# 06_LMS7002M_RF2.net
KiCad netlist of a schematic drawn in Altium Designer
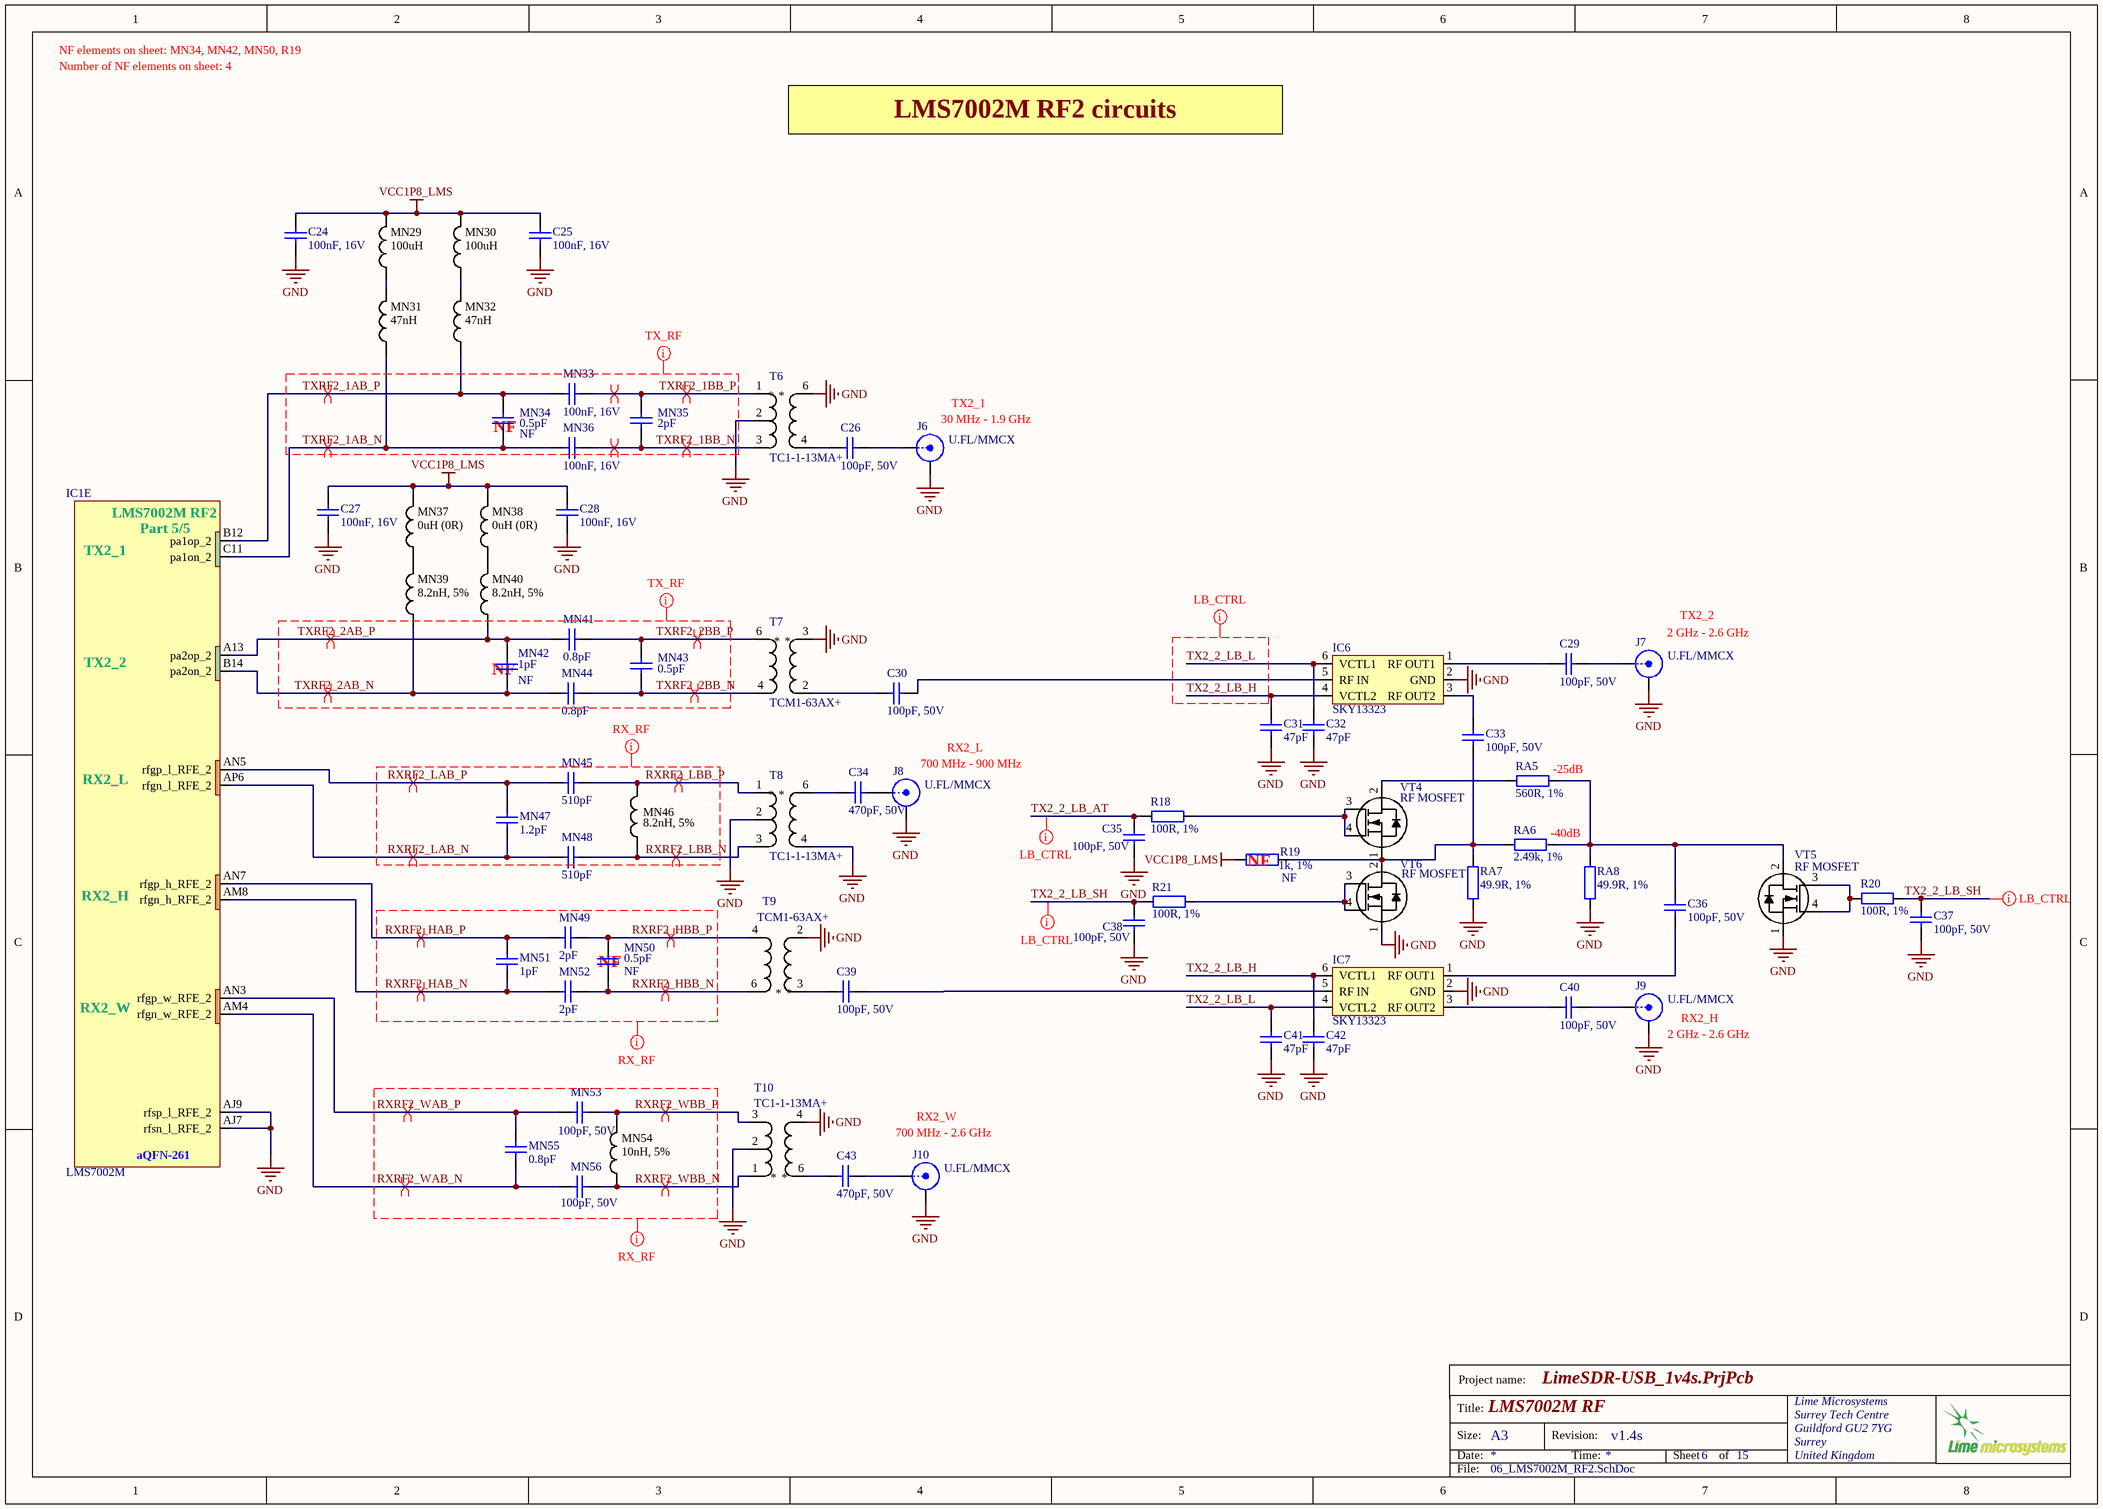
[diagram p0: 06_LMS7002M_RF2.SchDoc]

(export (version "E")
  (design (tool "Eeschema 10.0.6"))
  (components
    (comp (ref "C24")
      (value "100nF, 16V")
      (footprint "CAP0402")
      (fields
        (field (name "MANUFACTURER") "Murata Electronics")
        (field (name "TOLERANCE") "10 %")
        (field (name "MANUFACTURER PART NUMBER") "GRM155R71C104KA88D")
      )
      (libsource (lib "LimeMicroAltiumLib_schLib") (part "Cap_0402"))
    )
    (comp (ref "C25")
      (value "100nF, 16V")
      (footprint "CAP0402")
      (fields
        (field (name "MANUFACTURER") "Murata Electronics")
        (field (name "TOLERANCE") "10 %")
        (field (name "MANUFACTURER PART NUMBER") "GRM155R71C104KA88D")
      )
      (libsource (lib "LimeMicroAltiumLib_schLib") (part "Cap_0402"))
    )
    (comp (ref "C26")
      (value "100pF, 50V")
      (footprint "CAP0402")
      (fields (field (name "TOLERANCE") "±5%") (field (name "MANUFACTURER") "Yageo"))
      (libsource (lib "LimeMicroAltiumLib_schLib") (part "Cap_0402"))
    )
    (comp (ref "C27")
      (value "100nF, 16V")
      (footprint "CAP0402")
      (fields
        (field (name "MANUFACTURER") "Murata Electronics")
        (field (name "TOLERANCE") "10 %")
        (field (name "MANUFACTURER PART NUMBER") "GRM155R71C104KA88D")
      )
      (libsource (lib "LimeMicroAltiumLib_schLib") (part "Cap_0402"))
    )
    (comp (ref "C28")
      (value "100nF, 16V")
      (footprint "CAP0402")
      (fields
        (field (name "MANUFACTURER") "Murata Electronics")
        (field (name "TOLERANCE") "10 %")
        (field (name "MANUFACTURER PART NUMBER") "GRM155R71C104KA88D")
      )
      (libsource (lib "LimeMicroAltiumLib_schLib") (part "Cap_0402"))
    )
    (comp (ref "C29")
      (value "100pF, 50V")
      (footprint "CAP0402")
      (fields (field (name "TOLERANCE") "±5%") (field (name "MANUFACTURER") "Yageo"))
      (libsource (lib "LimeMicroAltiumLib_schLib") (part "Cap_0402"))
    )
    (comp (ref "C30")
      (value "100pF, 50V")
      (footprint "CAP0402")
      (fields (field (name "TOLERANCE") "±5%") (field (name "MANUFACTURER") "Yageo"))
      (libsource (lib "LimeMicroAltiumLib_schLib") (part "Cap_0402"))
    )
    (comp (ref "C31")
      (value "47pF")
      (footprint "CAP0402")
      (fields (field (name "TOLERANCE") "±1%") (field (name "MANUFACTURER") "TDK Corporation"))
      (libsource (lib "LimeMicroAltiumLib_schLib") (part "Cap_0402"))
    )
    (comp (ref "C32")
      (value "47pF")
      (footprint "CAP0402")
      (fields (field (name "TOLERANCE") "±1%") (field (name "MANUFACTURER") "TDK Corporation"))
      (libsource (lib "LimeMicroAltiumLib_schLib") (part "Cap_0402"))
    )
    (comp (ref "C33")
      (value "100pF, 50V")
      (footprint "CAP0402")
      (fields (field (name "TOLERANCE") "±5%") (field (name "MANUFACTURER") "Yageo"))
      (libsource (lib "LimeMicroAltiumLib_schLib") (part "Cap_0402"))
    )
    (comp (ref "C34")
      (value "470pF, 50V")
      (footprint "CAP0402")
      (fields
        (field (name "MANUFACTURER PART NUMBER") "C1005C0G1H471J050BA")
        (field (name "TOLERANCE") "±5%")
        (field (name "MANUFACTURER") "TDK Corporation")
      )
      (libsource (lib "LimeMicroAltiumLib_schLib") (part "Cap_0402"))
    )
    (comp (ref "C35")
      (value "100pF, 50V")
      (footprint "CAP0402")
      (fields (field (name "TOLERANCE") "±5%") (field (name "MANUFACTURER") "Yageo"))
      (libsource (lib "LimeMicroAltiumLib_schLib") (part "Cap_0402"))
    )
    (comp (ref "C36")
      (value "100pF, 50V")
      (footprint "CAP0402")
      (fields (field (name "TOLERANCE") "±5%") (field (name "MANUFACTURER") "Yageo"))
      (libsource (lib "LimeMicroAltiumLib_schLib") (part "Cap_0402"))
    )
    (comp (ref "C37")
      (value "100pF, 50V")
      (footprint "CAP0402")
      (fields (field (name "TOLERANCE") "±5%") (field (name "MANUFACTURER") "Yageo"))
      (libsource (lib "LimeMicroAltiumLib_schLib") (part "Cap_0402"))
    )
    (comp (ref "C38")
      (value "100pF, 50V")
      (footprint "CAP0402")
      (fields (field (name "TOLERANCE") "±5%") (field (name "MANUFACTURER") "Yageo"))
      (libsource (lib "LimeMicroAltiumLib_schLib") (part "Cap_0402"))
    )
    (comp (ref "C39")
      (value "100pF, 50V")
      (footprint "CAP0402")
      (fields (field (name "TOLERANCE") "±5%") (field (name "MANUFACTURER") "Yageo"))
      (libsource (lib "LimeMicroAltiumLib_schLib") (part "Cap_0402"))
    )
    (comp (ref "C40")
      (value "100pF, 50V")
      (footprint "CAP0402")
      (fields (field (name "TOLERANCE") "±5%") (field (name "MANUFACTURER") "Yageo"))
      (libsource (lib "LimeMicroAltiumLib_schLib") (part "Cap_0402"))
    )
    (comp (ref "C41")
      (value "47pF")
      (footprint "CAP0402")
      (fields (field (name "TOLERANCE") "±1%") (field (name "MANUFACTURER") "TDK Corporation"))
      (libsource (lib "LimeMicroAltiumLib_schLib") (part "Cap_0402"))
    )
    (comp (ref "C42")
      (value "47pF")
      (footprint "CAP0402")
      (fields (field (name "TOLERANCE") "±1%") (field (name "MANUFACTURER") "TDK Corporation"))
      (libsource (lib "LimeMicroAltiumLib_schLib") (part "Cap_0402"))
    )
    (comp (ref "C43")
      (value "470pF, 50V")
      (footprint "CAP0402")
      (fields
        (field (name "MANUFACTURER PART NUMBER") "C1005C0G1H471J050BA")
        (field (name "TOLERANCE") "±5%")
        (field (name "MANUFACTURER") "TDK Corporation")
      )
      (libsource (lib "LimeMicroAltiumLib_schLib") (part "Cap_0402"))
    )
    (comp (ref "IC1")
      (value "LMS7002M")
      (footprint "LMS7002M_v3")
      (fields (field (name "MANUFACTURER") "Lime Microsystems"))
      (libsource (lib "LimeMicroAltiumLib_schLib") (part "LMS7002M"))
    )
    (comp (ref "IC6")
      (value "SKY13323")
      (footprint "SKY13323-378LF")
      (description "SKY13323-378LF: 0.1-3.0 GHz GaAs SPDT Switch")
      (fields (field (name "MANUFACTURER") "Skyworks Solutions Inc."))
      (libsource (lib "LimeMicroAltiumLib_schLib") (part "SKY13323"))
    )
    (comp (ref "IC7")
      (value "SKY13323")
      (footprint "SKY13323-378LF")
      (description "SKY13323-378LF: 0.1-3.0 GHz GaAs SPDT Switch")
      (fields (field (name "MANUFACTURER") "Skyworks Solutions Inc."))
      (libsource (lib "LimeMicroAltiumLib_schLib") (part "SKY13323"))
    )
    (comp (ref "J6")
      (value "U.FL/MMCX")
      (footprint "MMCX_UFL_conn_u")
      (description "CONN UMC RCPT STR 50 OHM SMD")
      (fields (field (name "MANUFACTURER") "Molex, LLC"))
      (libsource (lib "LimeMicroAltiumLib_schLib") (part "RF_IF_connector"))
    )
    (comp (ref "J7")
      (value "U.FL/MMCX")
      (footprint "MMCX_UFL_conn_u")
      (description "CONN UMC RCPT STR 50 OHM SMD")
      (fields (field (name "MANUFACTURER") "Molex, LLC"))
      (libsource (lib "LimeMicroAltiumLib_schLib") (part "RF_IF_connector"))
    )
    (comp (ref "J8")
      (value "U.FL/MMCX")
      (footprint "MMCX_UFL_conn_u")
      (description "CONN UMC RCPT STR 50 OHM SMD")
      (fields (field (name "MANUFACTURER") "Molex, LLC"))
      (libsource (lib "LimeMicroAltiumLib_schLib") (part "RF_IF_connector"))
    )
    (comp (ref "J9")
      (value "U.FL/MMCX")
      (footprint "MMCX_UFL_conn_u")
      (description "CONN UMC RCPT STR 50 OHM SMD")
      (fields (field (name "MANUFACTURER") "Molex, LLC"))
      (libsource (lib "LimeMicroAltiumLib_schLib") (part "RF_IF_connector"))
    )
    (comp (ref "J10")
      (value "U.FL/MMCX")
      (footprint "MMCX_UFL_conn_u")
      (description "CONN UMC RCPT STR 50 OHM SMD")
      (fields (field (name "MANUFACTURER") "Molex, LLC"))
      (libsource (lib "LimeMicroAltiumLib_schLib") (part "RF_IF_connector"))
    )
    (comp (ref "MN29")
      (value "100uH")
      (footprint "RES0805")
      (fields
        (field (name "TOLERANCE") "±10%")
        (field (name "MANUFACTURER") "TDK Corporation")
        (field (name "MANUFACTURER PART NUMBER") "MLF2012C101KT000")
      )
      (libsource (lib "LimeMicroAltiumLib_schLib") (part "Inductor_0603"))
    )
    (comp (ref "MN30")
      (value "100uH")
      (footprint "RES0805")
      (fields
        (field (name "TOLERANCE") "±10%")
        (field (name "MANUFACTURER") "TDK Corporation")
        (field (name "MANUFACTURER PART NUMBER") "MLF2012C101KT000")
      )
      (libsource (lib "LimeMicroAltiumLib_schLib") (part "Inductor_0603"))
    )
    (comp (ref "MN31")
      (value "47nH")
      (footprint "RES0402")
      (fields
        (field (name "MANUFACTURER") "COILCRAFT")
        (field (name "MANUFACTURER PART NUMBER") "0402HP-47NXJLU")
      )
      (libsource (lib "LimeMicroAltiumLib_schLib") (part "Inductor_0603"))
    )
    (comp (ref "MN32")
      (value "47nH")
      (footprint "RES0402")
      (fields
        (field (name "MANUFACTURER") "COILCRAFT")
        (field (name "MANUFACTURER PART NUMBER") "0402HP-47NXJLU")
      )
      (libsource (lib "LimeMicroAltiumLib_schLib") (part "Inductor_0603"))
    )
    (comp (ref "MN33")
      (value "100nF, 16V")
      (footprint "CAP0402")
      (fields
        (field (name "MANUFACTURER") "Murata Electronics")
        (field (name "TOLERANCE") "10 %")
        (field (name "MANUFACTURER PART NUMBER") "GRM155R71C104KA88D")
      )
      (libsource (lib "LimeMicroAltiumLib_schLib") (part "Cap_0402"))
    )
    (comp (ref "MN34")
      (value "0.5pF")
      (footprint "CAP0402")
      (fields
        (field (name "ASSEMBLY INFO") "NF")
        (field (name "TOLERANCE") "±0.25pF")
        (field (name "MANUFACTURER") "Yageo")
      )
      (libsource (lib "LimeMicroAltiumLib_schLib") (part "Cap_0402"))
    )
    (comp (ref "MN35")
      (value "2pF")
      (footprint "CAP0402")
      (fields (field (name "MANUFACTURER PART NUMBER") "04025U2R0BAT2A") (field (name "MANUFACTURER") "AVX"))
      (libsource (lib "LimeMicroAltiumLib_schLib") (part "Cap_0402"))
    )
    (comp (ref "MN36")
      (value "100nF, 16V")
      (footprint "CAP0402")
      (fields
        (field (name "MANUFACTURER") "Murata Electronics")
        (field (name "TOLERANCE") "10 %")
        (field (name "MANUFACTURER PART NUMBER") "GRM155R71C104KA88D")
      )
      (libsource (lib "LimeMicroAltiumLib_schLib") (part "Cap_0402"))
    )
    (comp (ref "MN37")
      (value "0uH (0R)")
      (footprint "RES0805")
      (fields (field (name "MANUFACTURER") "BOURNS"))
      (libsource (lib "LimeMicroAltiumLib_schLib") (part "Inductor_0603"))
    )
    (comp (ref "MN38")
      (value "0uH (0R)")
      (footprint "RES0805")
      (fields (field (name "MANUFACTURER") "BOURNS"))
      (libsource (lib "LimeMicroAltiumLib_schLib") (part "Inductor_0603"))
    )
    (comp (ref "MN39")
      (value "8.2nH, 5%")
      (footprint "RES0402")
      (fields (field (name "MANUFACTURER") "COILCRAFT"))
      (libsource (lib "LimeMicroAltiumLib_schLib") (part "Inductor_0603"))
    )
    (comp (ref "MN40")
      (value "8.2nH, 5%")
      (footprint "RES0402")
      (fields (field (name "MANUFACTURER") "COILCRAFT"))
      (libsource (lib "LimeMicroAltiumLib_schLib") (part "Inductor_0603"))
    )
    (comp (ref "MN41")
      (value "0.8pF")
      (footprint "CAP0402")
      (fields
        (field (name "TOLERANCE") "±0.1pF")
        (field (name "MANUFACTURER") "Murata Electronics North America")
        (field (name "MANUFACTURER PART NUMBER") "GRM1555C1HR80BA01D")
      )
      (libsource (lib "LimeMicroAltiumLib_schLib") (part "Cap_0402"))
    )
    (comp (ref "MN42")
      (value "1pF")
      (footprint "CAP0402")
      (fields
        (field (name "ASSEMBLY INFO") "NF")
        (field (name "MANUFACTURER") "TDK Corporation")
        (field (name "TOLERANCE") "±0.1pF")
      )
      (libsource (lib "LimeMicroAltiumLib_schLib") (part "Cap_0402"))
    )
    (comp (ref "MN43")
      (value "0.5pF")
      (footprint "CAP0402")
      (fields (field (name "TOLERANCE") "±0.25pF") (field (name "MANUFACTURER") "Yageo"))
      (libsource (lib "LimeMicroAltiumLib_schLib") (part "Cap_0402"))
    )
    (comp (ref "MN44")
      (value "0.8pF")
      (footprint "CAP0402")
      (fields
        (field (name "TOLERANCE") "±0.1pF")
        (field (name "MANUFACTURER") "Murata Electronics North America")
        (field (name "MANUFACTURER PART NUMBER") "GRM1555C1HR80BA01D")
      )
      (libsource (lib "LimeMicroAltiumLib_schLib") (part "Cap_0402"))
    )
    (comp (ref "MN45")
      (value "510pF")
      (footprint "CAP0402")
      (fields
        (field (name "TOLERANCE") "±5%")
        (field (name "MANUFACTURER") "Murata Electronics North America")
        (field (name "MANUFACTURER PART NUMBER") "GRM1555C1H511JA01D")
      )
      (libsource (lib "LimeMicroAltiumLib_schLib") (part "Cap_0402"))
    )
    (comp (ref "MN46")
      (value "8.2nH, 5%")
      (footprint "RES0402")
      (fields (field (name "MANUFACTURER") "COILCRAFT"))
      (libsource (lib "LimeMicroAltiumLib_schLib") (part "Inductor_0603"))
    )
    (comp (ref "MN47")
      (value "1.2pF")
      (footprint "CAP0402")
      (fields
        (field (name "MANUFACTURER") "Murata Electronics North America")
        (field (name "MANUFACTURER PART NUMBER") "GRM1555C1H1R2CA01D")
        (field (name "TOLERANCE") "±0.25pF")
      )
      (libsource (lib "LimeMicroAltiumLib_schLib") (part "Cap_0402"))
    )
    (comp (ref "MN48")
      (value "510pF")
      (footprint "CAP0402")
      (fields
        (field (name "TOLERANCE") "±5%")
        (field (name "MANUFACTURER") "Murata Electronics North America")
        (field (name "MANUFACTURER PART NUMBER") "GRM1555C1H511JA01D")
      )
      (libsource (lib "LimeMicroAltiumLib_schLib") (part "Cap_0402"))
    )
    (comp (ref "MN49")
      (value "2pF")
      (footprint "CAP0402")
      (fields (field (name "MANUFACTURER PART NUMBER") "04025U2R0BAT2A") (field (name "MANUFACTURER") "AVX"))
      (libsource (lib "LimeMicroAltiumLib_schLib") (part "Cap_0402"))
    )
    (comp (ref "MN50")
      (value "0.5pF")
      (footprint "CAP0402")
      (fields
        (field (name "ASSEMBLY INFO") "NF")
        (field (name "TOLERANCE") "±0.25pF")
        (field (name "MANUFACTURER") "Yageo")
      )
      (libsource (lib "LimeMicroAltiumLib_schLib") (part "Cap_0402"))
    )
    (comp (ref "MN51")
      (value "1pF")
      (footprint "CAP0402")
      (fields (field (name "MANUFACTURER") "TDK Corporation") (field (name "TOLERANCE") "±0.1pF"))
      (libsource (lib "LimeMicroAltiumLib_schLib") (part "Cap_0402"))
    )
    (comp (ref "MN52")
      (value "2pF")
      (footprint "CAP0402")
      (fields (field (name "MANUFACTURER PART NUMBER") "04025U2R0BAT2A") (field (name "MANUFACTURER") "AVX"))
      (libsource (lib "LimeMicroAltiumLib_schLib") (part "Cap_0402"))
    )
    (comp (ref "MN53")
      (value "100pF, 50V")
      (footprint "CAP0402")
      (fields (field (name "TOLERANCE") "±5%") (field (name "MANUFACTURER") "Yageo"))
      (libsource (lib "LimeMicroAltiumLib_schLib") (part "Cap_0402"))
    )
    (comp (ref "MN54")
      (value "10nH, 5%")
      (footprint "RES0402")
      (fields (field (name "MANUFACTURER") "COILCRAFT"))
      (libsource (lib "LimeMicroAltiumLib_schLib") (part "Inductor_0603"))
    )
    (comp (ref "MN55")
      (value "0.8pF")
      (footprint "CAP0402")
      (fields
        (field (name "TOLERANCE") "±0.1pF")
        (field (name "MANUFACTURER") "Murata Electronics North America")
        (field (name "MANUFACTURER PART NUMBER") "GRM1555C1HR80BA01D")
      )
      (libsource (lib "LimeMicroAltiumLib_schLib") (part "Cap_0402"))
    )
    (comp (ref "MN56")
      (value "100pF, 50V")
      (footprint "CAP0402")
      (fields (field (name "TOLERANCE") "±5%") (field (name "MANUFACTURER") "Yageo"))
      (libsource (lib "LimeMicroAltiumLib_schLib") (part "Cap_0402"))
    )
    (comp (ref "R18")
      (value "100R, 1%")
      (footprint "RES0402")
      (fields (field (name "TOLERANCE") "±1%") (field (name "MANUFACTURER") "Stackpole Electronics Inc."))
      (libsource (lib "LimeFPGAboard_schLib") (part "Res_0402"))
    )
    (comp (ref "R19")
      (value "1k, 1%")
      (footprint "RES0402")
      (fields
        (field (name "ASSEMBLY INFO") "NF")
        (field (name "MANUFACTURER") "Stackpole Electronics Inc")
        (field (name "TOLERANCE") "±1%")
      )
      (libsource (lib "LimeMicroAltiumLib_schLib") (part "Res_0402"))
    )
    (comp (ref "R20")
      (value "100R, 1%")
      (footprint "RES0402")
      (fields (field (name "TOLERANCE") "±1%") (field (name "MANUFACTURER") "Stackpole Electronics Inc."))
      (libsource (lib "LimeFPGAboard_schLib") (part "Res_0402"))
    )
    (comp (ref "R21")
      (value "100R, 1%")
      (footprint "RES0402")
      (fields (field (name "TOLERANCE") "±1%") (field (name "MANUFACTURER") "Stackpole Electronics Inc."))
      (libsource (lib "LimeFPGAboard_schLib") (part "Res_0402"))
    )
    (comp (ref "RA5")
      (value "560R, 1%")
      (footprint "RES0402")
      (fields
        (field (name "MANUFACTURER PART NUMBER") "CRCW0402560RFKED")
        (field (name "TOLERANCE") "±1%")
        (field (name "MANUFACTURER") "Vishay Dale")
      )
      (libsource (lib "LimeMicroAltiumLib_schLib") (part "Res_0402"))
    )
    (comp (ref "RA6")
      (value "2.49k, 1%")
      (footprint "RES0402")
      (fields
        (field (name "TOLERANCE") "±1%")
        (field (name "MANUFACTURER PART NUMBER") "RC0402FR-072K49L")
        (field (name "MANUFACTURER") "Yageo")
      )
      (libsource (lib "LimeMicroAltiumLib_schLib") (part "Res_0402"))
    )
    (comp (ref "RA7")
      (value "49.9R, 1%")
      (footprint "RES0402")
      (fields
        (field (name "TOLERANCE") "±1%")
        (field (name "MANUFACTURER") "Samsung Electro-Mechanics America, Inc.")
        (field (name "MANUFACTURER PART NUMBER") "RC1005F49R9CS")
      )
      (libsource (lib "LimeMicroAltiumLib_schLib") (part "Res_0402"))
    )
    (comp (ref "RA8")
      (value "49.9R, 1%")
      (footprint "RES0402")
      (fields
        (field (name "TOLERANCE") "±1%")
        (field (name "MANUFACTURER") "Samsung Electro-Mechanics America, Inc.")
        (field (name "MANUFACTURER PART NUMBER") "RC1005F49R9CS")
      )
      (libsource (lib "LimeMicroAltiumLib_schLib") (part "Res_0402"))
    )
    (comp (ref "T6")
      (value "TC1-1-13MA+")
      (footprint "TC1-1-13MA+_v2")
      (fields (field (name "MANUFACTURER") "Mini-Circuits"))
      (libsource (lib "LimeMicroAltiumLib_schLib") (part "Balun"))
    )
    (comp (ref "T7")
      (value "TCM1-63AX+")
      (footprint "TCM1-63AX+_v2")
      (fields (field (name "MANUFACTURER") "Mini-circuits"))
      (libsource (lib "") (part "Balun_v2_1"))
    )
    (comp (ref "T8")
      (value "TC1-1-13MA+")
      (footprint "TC1-1-13MA+_v2")
      (fields (field (name "MANUFACTURER") "Mini-Circuits"))
      (libsource (lib "LimeMicroAltiumLib_schLib") (part "Balun"))
    )
    (comp (ref "T9")
      (value "TCM1-63AX+")
      (footprint "TCM1-63AX+_v2")
      (fields (field (name "MANUFACTURER") "Mini-circuits"))
      (libsource (lib "LimeMicroAltiumLib_schLib") (part "Balun_v2"))
    )
    (comp (ref "T10")
      (value "TC1-1-13MA+")
      (footprint "TC1-1-13MA+_v2")
      (fields (field (name "MANUFACTURER") "Mini-Circuits"))
      (libsource (lib "") (part "Balun_1"))
    )
    (comp (ref "VT4")
      (value "RF MOSFET")
      (footprint "BF1105R_SOT143R4")
      (fields (field (name "MANUFACTURER") "NXP Semiconductors"))
      (libsource (lib "LimeMicroAltiumLib_schLib") (part "BF1105R,215"))
    )
    (comp (ref "VT5")
      (value "RF MOSFET")
      (footprint "BF1105R_SOT143R4")
      (fields (field (name "MANUFACTURER") "NXP Semiconductors"))
      (libsource (lib "LimeMicroAltiumLib_schLib") (part "BF1105R,215"))
    )
    (comp (ref "VT6")
      (value "RF MOSFET")
      (footprint "BF1105R_SOT143R4")
      (fields (field (name "MANUFACTURER") "NXP Semiconductors"))
      (libsource (lib "LimeMicroAltiumLib_schLib") (part "BF1105R,215"))
    )
  )
  (nets
    (net (code "1") (name "/RXRF2_HAB_N") (class "Default")
      (node (ref "IC1") (pin "AM8") (pinfunction "rfgn_h_RFE_2_AM8") (pintype "passive"))
      (node (ref "MN51") (pin "1") (pinfunction "1_1") (pintype "passive"))
      (node (ref "MN52") (pin "2") (pinfunction "2_2") (pintype "passive"))
    )
    (net (code "2") (name "/RXRF2_HAB_P") (class "Default")
      (node (ref "IC1") (pin "AN7") (pinfunction "rfgp_h_RFE_2_AN7") (pintype "passive"))
      (node (ref "MN49") (pin "2") (pinfunction "2_2") (pintype "passive"))
      (node (ref "MN51") (pin "2") (pinfunction "2_2") (pintype "passive"))
    )
    (net (code "3") (name "/RXRF2_HBB_N") (class "Default")
      (node (ref "MN50") (pin "1") (pinfunction "1_1") (pintype "passive"))
      (node (ref "MN52") (pin "1") (pinfunction "1_1") (pintype "passive"))
      (node (ref "T9") (pin "6") (pinfunction "6_6") (pintype "passive"))
    )
    (net (code "4") (name "/RXRF2_HBB_P") (class "Default")
      (node (ref "MN49") (pin "1") (pinfunction "1_1") (pintype "passive"))
      (node (ref "MN50") (pin "2") (pinfunction "2_2") (pintype "passive"))
      (node (ref "T9") (pin "4") (pinfunction "4_4") (pintype "passive"))
    )
    (net (code "5") (name "/RXRF2_LAB_N") (class "Default")
      (node (ref "IC1") (pin "AP6") (pinfunction "rfgn_l_RFE_2_AP6") (pintype "passive"))
      (node (ref "MN47") (pin "1") (pinfunction "1_1") (pintype "passive"))
      (node (ref "MN48") (pin "2") (pinfunction "2_2") (pintype "passive"))
    )
    (net (code "6") (name "/RXRF2_LAB_P") (class "Default")
      (node (ref "IC1") (pin "AN5") (pinfunction "rfgp_l_RFE_2_AN5") (pintype "passive"))
      (node (ref "MN45") (pin "2") (pinfunction "2_2") (pintype "passive"))
      (node (ref "MN47") (pin "2") (pinfunction "2_2") (pintype "passive"))
    )
    (net (code "7") (name "/RXRF2_LBB_N") (class "Default")
      (node (ref "MN46") (pin "1") (pinfunction "1_1") (pintype "passive"))
      (node (ref "MN48") (pin "1") (pinfunction "1_1") (pintype "passive"))
      (node (ref "T8") (pin "3") (pinfunction "3_3") (pintype "passive"))
    )
    (net (code "8") (name "/RXRF2_LBB_P") (class "Default")
      (node (ref "MN45") (pin "1") (pinfunction "1_1") (pintype "passive"))
      (node (ref "MN46") (pin "2") (pinfunction "2_2") (pintype "passive"))
      (node (ref "T8") (pin "1") (pinfunction "1_1") (pintype "passive"))
    )
    (net (code "9") (name "/RXRF2_WAB_N") (class "Default")
      (node (ref "IC1") (pin "AM4") (pinfunction "rfgn_w_RFE_2_AM4") (pintype "passive"))
      (node (ref "MN55") (pin "2") (pinfunction "2_2") (pintype "passive"))
      (node (ref "MN56") (pin "2") (pinfunction "2_2") (pintype "passive"))
    )
    (net (code "10") (name "/RXRF2_WAB_P") (class "Default")
      (node (ref "IC1") (pin "AN3") (pinfunction "rfgp_w_RFE_2_AN3") (pintype "passive"))
      (node (ref "MN53") (pin "2") (pinfunction "2_2") (pintype "passive"))
      (node (ref "MN55") (pin "1") (pinfunction "1_1") (pintype "passive"))
    )
    (net (code "11") (name "/RXRF2_WBB_N") (class "Default")
      (node (ref "MN54") (pin "1") (pinfunction "1_1") (pintype "passive"))
      (node (ref "MN56") (pin "1") (pinfunction "1_1") (pintype "passive"))
      (node (ref "T10") (pin "1") (pinfunction "1_1") (pintype "passive"))
    )
    (net (code "12") (name "/RXRF2_WBB_P") (class "Default")
      (node (ref "MN53") (pin "1") (pinfunction "1_1") (pintype "passive"))
      (node (ref "MN54") (pin "2") (pinfunction "2_2") (pintype "passive"))
      (node (ref "T10") (pin "3") (pinfunction "3_3") (pintype "passive"))
    )
    (net (code "13") (name "/TX2_2_LB_AT") (class "Default")
      (node (ref "C35") (pin "1") (pinfunction "1_1") (pintype "passive"))
      (node (ref "R18") (pin "2") (pinfunction "2_2") (pintype "passive"))
    )
    (net (code "14") (name "/TX2_2_LB_H") (class "Default")
      (node (ref "C31") (pin "2") (pinfunction "2_2") (pintype "passive"))
      (node (ref "C42") (pin "2") (pinfunction "2_2") (pintype "passive"))
      (node (ref "IC6") (pin "4") (pinfunction "VCTL2_4") (pintype "input"))
      (node (ref "IC7") (pin "6") (pinfunction "VCTL1_6") (pintype "input"))
    )
    (net (code "15") (name "/TX2_2_LB_L") (class "Default")
      (node (ref "C32") (pin "2") (pinfunction "2_2") (pintype "passive"))
      (node (ref "C41") (pin "2") (pinfunction "2_2") (pintype "passive"))
      (node (ref "IC6") (pin "6") (pinfunction "VCTL1_6") (pintype "input"))
      (node (ref "IC7") (pin "4") (pinfunction "VCTL2_4") (pintype "input"))
    )
    (net (code "16") (name "/TX2_2_LB_SH") (class "Default")
      (node (ref "C37") (pin "1") (pinfunction "1_1") (pintype "passive"))
      (node (ref "C38") (pin "1") (pinfunction "1_1") (pintype "passive"))
      (node (ref "R20") (pin "1") (pinfunction "1_1") (pintype "passive"))
      (node (ref "R21") (pin "2") (pinfunction "2_2") (pintype "passive"))
    )
    (net (code "17") (name "/TXRF2_1AB_N") (class "Default")
      (node (ref "IC1") (pin "C11") (pinfunction "pa1on_2_C11") (pintype "passive"))
      (node (ref "MN31") (pin "1") (pinfunction "1_1") (pintype "passive"))
      (node (ref "MN34") (pin "1") (pinfunction "1_1") (pintype "passive"))
      (node (ref "MN36") (pin "1") (pinfunction "1_1") (pintype "passive"))
    )
    (net (code "18") (name "/TXRF2_1AB_P") (class "Default")
      (node (ref "IC1") (pin "B12") (pinfunction "pa1op_2_B12") (pintype "passive"))
      (node (ref "MN32") (pin "1") (pinfunction "1_1") (pintype "passive"))
      (node (ref "MN33") (pin "2") (pinfunction "2_2") (pintype "passive"))
      (node (ref "MN34") (pin "2") (pinfunction "2_2") (pintype "passive"))
    )
    (net (code "19") (name "/TXRF2_1BB_N") (class "Default")
      (node (ref "MN35") (pin "1") (pinfunction "1_1") (pintype "passive"))
      (node (ref "MN36") (pin "2") (pinfunction "2_2") (pintype "passive"))
      (node (ref "T6") (pin "3") (pinfunction "3_3") (pintype "passive"))
    )
    (net (code "20") (name "/TXRF2_1BB_P") (class "Default")
      (node (ref "MN33") (pin "1") (pinfunction "1_1") (pintype "passive"))
      (node (ref "MN35") (pin "2") (pinfunction "2_2") (pintype "passive"))
      (node (ref "T6") (pin "1") (pinfunction "1_1") (pintype "passive"))
    )
    (net (code "21") (name "/TXRF2_2AB_N") (class "Default")
      (node (ref "IC1") (pin "B14") (pinfunction "pa2on_2_B14") (pintype "passive"))
      (node (ref "MN39") (pin "1") (pinfunction "1_1") (pintype "passive"))
      (node (ref "MN42") (pin "2") (pinfunction "2_2") (pintype "passive"))
      (node (ref "MN44") (pin "2") (pinfunction "2_2") (pintype "passive"))
    )
    (net (code "22") (name "/TXRF2_2AB_P") (class "Default")
      (node (ref "IC1") (pin "A13") (pinfunction "pa2op_2_A13") (pintype "passive"))
      (node (ref "MN40") (pin "1") (pinfunction "1_1") (pintype "passive"))
      (node (ref "MN41") (pin "2") (pinfunction "2_2") (pintype "passive"))
      (node (ref "MN42") (pin "1") (pinfunction "1_1") (pintype "passive"))
    )
    (net (code "23") (name "/TXRF2_2BB_N") (class "Default")
      (node (ref "MN43") (pin "1") (pinfunction "1_1") (pintype "passive"))
      (node (ref "MN44") (pin "1") (pinfunction "1_1") (pintype "passive"))
      (node (ref "T7") (pin "4") (pinfunction "4_4") (pintype "passive"))
    )
    (net (code "24") (name "/TXRF2_2BB_P") (class "Default")
      (node (ref "MN41") (pin "1") (pinfunction "1_1") (pintype "passive"))
      (node (ref "MN43") (pin "2") (pinfunction "2_2") (pintype "passive"))
      (node (ref "T7") (pin "6") (pinfunction "6_6") (pintype "passive"))
    )
    (net (code "25") (name "GND") (class "Default")
      (node (ref "C24") (pin "1") (pinfunction "1_1") (pintype "passive"))
      (node (ref "C25") (pin "1") (pinfunction "1_1") (pintype "passive"))
      (node (ref "C27") (pin "1") (pinfunction "1_1") (pintype "passive"))
      (node (ref "C28") (pin "1") (pinfunction "1_1") (pintype "passive"))
      (node (ref "C31") (pin "1") (pinfunction "1_1") (pintype "passive"))
      (node (ref "C32") (pin "1") (pinfunction "1_1") (pintype "passive"))
      (node (ref "C35") (pin "2") (pinfunction "2_2") (pintype "passive"))
      (node (ref "C37") (pin "2") (pinfunction "2_2") (pintype "passive"))
      (node (ref "C38") (pin "2") (pinfunction "2_2") (pintype "passive"))
      (node (ref "C41") (pin "1") (pinfunction "1_1") (pintype "passive"))
      (node (ref "C42") (pin "1") (pinfunction "1_1") (pintype "passive"))
      (node (ref "IC1") (pin "AJ7") (pinfunction "rfsn_l_RFE_2_AJ7") (pintype "passive"))
      (node (ref "IC1") (pin "AJ9") (pinfunction "rfsp_l_RFE_2_AJ9") (pintype "passive"))
      (node (ref "IC6") (pin "2") (pinfunction "GND_2") (pintype "passive"))
      (node (ref "IC7") (pin "2") (pinfunction "GND_2") (pintype "passive"))
      (node (ref "J10") (pin "2") (pinfunction "Y_2") (pintype "passive"))
      (node (ref "J6") (pin "2") (pinfunction "Y_2") (pintype "passive"))
      (node (ref "J7") (pin "2") (pinfunction "Y_2") (pintype "passive"))
      (node (ref "J8") (pin "2") (pinfunction "Y_2") (pintype "passive"))
      (node (ref "J9") (pin "2") (pinfunction "Y_2") (pintype "passive"))
      (node (ref "RA7") (pin "1") (pinfunction "1_1") (pintype "passive"))
      (node (ref "RA8") (pin "1") (pinfunction "1_1") (pintype "passive"))
      (node (ref "T10") (pin "2") (pinfunction "2_2") (pintype "passive"))
      (node (ref "T10") (pin "4") (pinfunction "4_4") (pintype "passive"))
      (node (ref "T6") (pin "2") (pinfunction "2_2") (pintype "passive"))
      (node (ref "T6") (pin "6") (pinfunction "6_6") (pintype "passive"))
      (node (ref "T7") (pin "3") (pinfunction "3_3") (pintype "passive"))
      (node (ref "T8") (pin "2") (pinfunction "2_2") (pintype "passive"))
      (node (ref "T8") (pin "4") (pinfunction "4_4") (pintype "passive"))
      (node (ref "T9") (pin "2") (pinfunction "2_2") (pintype "passive"))
      (node (ref "VT5") (pin "1") (pinfunction "S_1") (pintype "passive"))
      (node (ref "VT6") (pin "1") (pinfunction "S_1") (pintype "passive"))
    )
    (net (code "26") (name "Net-(C26-Pad2)") (class "Default")
      (node (ref "C26") (pin "2") (pinfunction "2_2") (pintype "passive"))
      (node (ref "T6") (pin "4") (pinfunction "4_4") (pintype "passive"))
    )
    (net (code "27") (name "Net-(C30-Pad2)") (class "Default")
      (node (ref "C30") (pin "2") (pinfunction "2_2") (pintype "passive"))
      (node (ref "T7") (pin "2") (pinfunction "2_2") (pintype "passive"))
    )
    (net (code "28") (name "Net-(C34-Pad2)") (class "Default")
      (node (ref "C34") (pin "2") (pinfunction "2_2") (pintype "passive"))
      (node (ref "T8") (pin "6") (pinfunction "6_6") (pintype "passive"))
    )
    (net (code "29") (name "Net-(C39-Pad2)") (class "Default")
      (node (ref "C39") (pin "2") (pinfunction "2_2") (pintype "passive"))
      (node (ref "T9") (pin "3") (pinfunction "3_3") (pintype "passive"))
    )
    (net (code "30") (name "Net-(C43-Pad2)") (class "Default")
      (node (ref "C43") (pin "2") (pinfunction "2_2") (pintype "passive"))
      (node (ref "T10") (pin "6") (pinfunction "6_6") (pintype "passive"))
    )
    (net (code "31") (name "Net-(IC6-RF_IN)") (class "Default")
      (node (ref "C30") (pin "1") (pinfunction "1_1") (pintype "passive"))
      (node (ref "IC6") (pin "5") (pinfunction "RF_IN_5") (pintype "input"))
    )
    (net (code "32") (name "Net-(IC6-RF_OUT1)") (class "Default")
      (node (ref "C29") (pin "2") (pinfunction "2_2") (pintype "passive"))
      (node (ref "IC6") (pin "1") (pinfunction "RF_OUT1_1") (pintype "output"))
    )
    (net (code "33") (name "Net-(IC6-RF_OUT2)") (class "Default")
      (node (ref "C33") (pin "1") (pinfunction "1_1") (pintype "passive"))
      (node (ref "IC6") (pin "3") (pinfunction "RF_OUT2_3") (pintype "output"))
    )
    (net (code "34") (name "Net-(IC7-RF_IN)") (class "Default")
      (node (ref "C39") (pin "1") (pinfunction "1_1") (pintype "passive"))
      (node (ref "IC7") (pin "5") (pinfunction "RF_IN_5") (pintype "input"))
    )
    (net (code "35") (name "Net-(IC7-RF_OUT1)") (class "Default")
      (node (ref "C36") (pin "2") (pinfunction "2_2") (pintype "passive"))
      (node (ref "IC7") (pin "1") (pinfunction "RF_OUT1_1") (pintype "output"))
    )
    (net (code "36") (name "Net-(IC7-RF_OUT2)") (class "Default")
      (node (ref "C40") (pin "2") (pinfunction "2_2") (pintype "passive"))
      (node (ref "IC7") (pin "3") (pinfunction "RF_OUT2_3") (pintype "output"))
    )
    (net (code "37") (name "Net-(J6-X)") (class "Default")
      (node (ref "C26") (pin "1") (pinfunction "1_1") (pintype "passive"))
      (node (ref "J6") (pin "1") (pinfunction "X_1") (pintype "passive"))
    )
    (net (code "38") (name "Net-(J7-X)") (class "Default")
      (node (ref "C29") (pin "1") (pinfunction "1_1") (pintype "passive"))
      (node (ref "J7") (pin "1") (pinfunction "X_1") (pintype "passive"))
    )
    (net (code "39") (name "Net-(J8-X)") (class "Default")
      (node (ref "C34") (pin "1") (pinfunction "1_1") (pintype "passive"))
      (node (ref "J8") (pin "1") (pinfunction "X_1") (pintype "passive"))
    )
    (net (code "40") (name "Net-(J9-X)") (class "Default")
      (node (ref "C40") (pin "1") (pinfunction "1_1") (pintype "passive"))
      (node (ref "J9") (pin "1") (pinfunction "X_1") (pintype "passive"))
    )
    (net (code "41") (name "Net-(J10-X)") (class "Default")
      (node (ref "C43") (pin "1") (pinfunction "1_1") (pintype "passive"))
      (node (ref "J10") (pin "1") (pinfunction "X_1") (pintype "passive"))
    )
    (net (code "42") (name "Net-(MN29-Pad1)") (class "Default")
      (node (ref "MN29") (pin "1") (pinfunction "1_1") (pintype "passive"))
      (node (ref "MN31") (pin "2") (pinfunction "2_2") (pintype "passive"))
    )
    (net (code "43") (name "Net-(MN30-Pad1)") (class "Default")
      (node (ref "MN30") (pin "1") (pinfunction "1_1") (pintype "passive"))
      (node (ref "MN32") (pin "2") (pinfunction "2_2") (pintype "passive"))
    )
    (net (code "44") (name "Net-(MN37-Pad1)") (class "Default")
      (node (ref "MN37") (pin "1") (pinfunction "1_1") (pintype "passive"))
      (node (ref "MN39") (pin "2") (pinfunction "2_2") (pintype "passive"))
    )
    (net (code "45") (name "Net-(MN38-Pad1)") (class "Default")
      (node (ref "MN38") (pin "1") (pinfunction "1_1") (pintype "passive"))
      (node (ref "MN40") (pin "2") (pinfunction "2_2") (pintype "passive"))
    )
    (net (code "46") (name "Net-(VT4-D)") (class "Default")
      (node (ref "RA5") (pin "2") (pinfunction "2_2") (pintype "passive"))
      (node (ref "VT4") (pin "2") (pinfunction "D_2") (pintype "passive"))
    )
    (net (code "47") (name "Net-(VT4-G1)") (class "Default")
      (node (ref "R18") (pin "1") (pinfunction "1_1") (pintype "passive"))
      (node (ref "VT4") (pin "3") (pinfunction "G2_3") (pintype "passive"))
      (node (ref "VT4") (pin "4") (pinfunction "G1_4") (pintype "passive"))
    )
    (net (code "48") (name "Net-(VT4-S)") (class "Default")
      (node (ref "C33") (pin "2") (pinfunction "2_2") (pintype "passive"))
      (node (ref "R19") (pin "1") (pinfunction "1_1") (pintype "passive"))
      (node (ref "RA6") (pin "1") (pinfunction "1_1") (pintype "passive"))
      (node (ref "RA7") (pin "2") (pinfunction "2_2") (pintype "passive"))
      (node (ref "VT4") (pin "1") (pinfunction "S_1") (pintype "passive"))
      (node (ref "VT6") (pin "2") (pinfunction "D_2") (pintype "passive"))
    )
    (net (code "49") (name "Net-(VT5-D)") (class "Default")
      (node (ref "C36") (pin "1") (pinfunction "1_1") (pintype "passive"))
      (node (ref "RA5") (pin "1") (pinfunction "1_1") (pintype "passive"))
      (node (ref "RA6") (pin "2") (pinfunction "2_2") (pintype "passive"))
      (node (ref "RA8") (pin "2") (pinfunction "2_2") (pintype "passive"))
      (node (ref "VT5") (pin "2") (pinfunction "D_2") (pintype "passive"))
    )
    (net (code "50") (name "Net-(VT5-G1)") (class "Default")
      (node (ref "R20") (pin "2") (pinfunction "2_2") (pintype "passive"))
      (node (ref "VT5") (pin "3") (pinfunction "G2_3") (pintype "passive"))
      (node (ref "VT5") (pin "4") (pinfunction "G1_4") (pintype "passive"))
    )
    (net (code "51") (name "Net-(VT6-G1)") (class "Default")
      (node (ref "R21") (pin "1") (pinfunction "1_1") (pintype "passive"))
      (node (ref "VT6") (pin "3") (pinfunction "G2_3") (pintype "passive"))
      (node (ref "VT6") (pin "4") (pinfunction "G1_4") (pintype "passive"))
    )
    (net (code "52") (name "VCC1P8_LMS") (class "Default")
      (node (ref "C24") (pin "2") (pinfunction "2_2") (pintype "passive"))
      (node (ref "C25") (pin "2") (pinfunction "2_2") (pintype "passive"))
      (node (ref "C27") (pin "2") (pinfunction "2_2") (pintype "passive"))
      (node (ref "C28") (pin "2") (pinfunction "2_2") (pintype "passive"))
      (node (ref "MN29") (pin "2") (pinfunction "2_2") (pintype "passive"))
      (node (ref "MN30") (pin "2") (pinfunction "2_2") (pintype "passive"))
      (node (ref "MN37") (pin "2") (pinfunction "2_2") (pintype "passive"))
      (node (ref "MN38") (pin "2") (pinfunction "2_2") (pintype "passive"))
      (node (ref "R19") (pin "2") (pinfunction "2_2") (pintype "passive"))
    )
  )
)
